# 8led-indicator.net
KiCad netlist of a schematic drawn in EAGLE
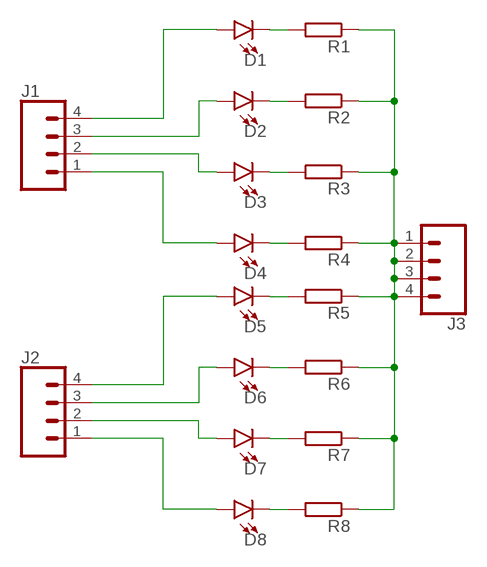
[diagram p0: schematic, sheet 1]

(export (version "E")
  (design (tool "Eeschema 10.0.6"))
  (components
    (comp (ref "D1")
      (value "LED0603")
      (footprint "eagle-import:LED-0603")
      (libsource (lib "eagle-import") (part "LED0603"))
    )
    (comp (ref "D2")
      (value "LED0603")
      (footprint "eagle-import:LED-0603")
      (libsource (lib "eagle-import") (part "LED0603"))
    )
    (comp (ref "D3")
      (value "LED0603")
      (footprint "eagle-import:LED-0603")
      (libsource (lib "eagle-import") (part "LED0603"))
    )
    (comp (ref "D4")
      (value "LED0603")
      (footprint "eagle-import:LED-0603")
      (libsource (lib "eagle-import") (part "LED0603"))
    )
    (comp (ref "D5")
      (value "LED0603")
      (footprint "eagle-import:LED-0603")
      (libsource (lib "eagle-import") (part "LED0603"))
    )
    (comp (ref "D6")
      (value "LED0603")
      (footprint "eagle-import:LED-0603")
      (libsource (lib "eagle-import") (part "LED0603"))
    )
    (comp (ref "D7")
      (value "LED0603")
      (footprint "eagle-import:LED-0603")
      (libsource (lib "eagle-import") (part "LED0603"))
    )
    (comp (ref "D8")
      (value "LED0603")
      (footprint "eagle-import:LED-0603")
      (libsource (lib "eagle-import") (part "LED0603"))
    )
    (comp (ref "J1")
      (value "CONN_04LOCK")
      (footprint "eagle-import:1X04_LOCK")
      (libsource (lib "eagle-import") (part "CONN_04LOCK"))
    )
    (comp (ref "J2")
      (value "CONN_04LOCK")
      (footprint "eagle-import:1X04_LOCK")
      (libsource (lib "eagle-import") (part "CONN_04LOCK"))
    )
    (comp (ref "J3")
      (value "CONN_04LOCK")
      (footprint "eagle-import:1X04_LOCK")
      (libsource (lib "eagle-import") (part "CONN_04LOCK"))
    )
    (comp (ref "R1")
      (value "RESISTOR-EU_R0603")
      (footprint "eagle-import:R0603")
      (libsource (lib "eagle-import") (part "RESISTOR-EU_R0603"))
    )
    (comp (ref "R2")
      (value "RESISTOR-EU_R0603")
      (footprint "eagle-import:R0603")
      (libsource (lib "eagle-import") (part "RESISTOR-EU_R0603"))
    )
    (comp (ref "R3")
      (value "RESISTOR-EU_R0603")
      (footprint "eagle-import:R0603")
      (libsource (lib "eagle-import") (part "RESISTOR-EU_R0603"))
    )
    (comp (ref "R4")
      (value "RESISTOR-EU_R0603")
      (footprint "eagle-import:R0603")
      (libsource (lib "eagle-import") (part "RESISTOR-EU_R0603"))
    )
    (comp (ref "R5")
      (value "RESISTOR-EU_R0603")
      (footprint "eagle-import:R0603")
      (libsource (lib "eagle-import") (part "RESISTOR-EU_R0603"))
    )
    (comp (ref "R6")
      (value "RESISTOR-EU_R0603")
      (footprint "eagle-import:R0603")
      (libsource (lib "eagle-import") (part "RESISTOR-EU_R0603"))
    )
    (comp (ref "R7")
      (value "RESISTOR-EU_R0603")
      (footprint "eagle-import:R0603")
      (libsource (lib "eagle-import") (part "RESISTOR-EU_R0603"))
    )
    (comp (ref "R8")
      (value "RESISTOR-EU_R0603")
      (footprint "eagle-import:R0603")
      (libsource (lib "eagle-import") (part "RESISTOR-EU_R0603"))
    )
  )
  (nets
    (net (code "1") (name "Net-(D1-PadA)") (class "Default")
      (node (ref "D1") (pin "A") (pinfunction "A_A") (pintype "passive"))
      (node (ref "J1") (pin "4") (pinfunction "4_4") (pintype "passive"))
    )
    (net (code "2") (name "Net-(D1-PadC)") (class "Default")
      (node (ref "D1") (pin "C") (pinfunction "C_C") (pintype "passive"))
      (node (ref "R1") (pin "2") (pinfunction "2_2") (pintype "passive"))
    )
    (net (code "3") (name "Net-(D2-PadA)") (class "Default")
      (node (ref "D2") (pin "A") (pinfunction "A_A") (pintype "passive"))
      (node (ref "J1") (pin "3") (pinfunction "3_3") (pintype "passive"))
    )
    (net (code "4") (name "Net-(D2-PadC)") (class "Default")
      (node (ref "D2") (pin "C") (pinfunction "C_C") (pintype "passive"))
      (node (ref "R2") (pin "2") (pinfunction "2_2") (pintype "passive"))
    )
    (net (code "5") (name "Net-(D3-PadA)") (class "Default")
      (node (ref "D3") (pin "A") (pinfunction "A_A") (pintype "passive"))
      (node (ref "J1") (pin "2") (pinfunction "2_2") (pintype "passive"))
    )
    (net (code "6") (name "Net-(D3-PadC)") (class "Default")
      (node (ref "D3") (pin "C") (pinfunction "C_C") (pintype "passive"))
      (node (ref "R3") (pin "2") (pinfunction "2_2") (pintype "passive"))
    )
    (net (code "7") (name "Net-(D4-PadA)") (class "Default")
      (node (ref "D4") (pin "A") (pinfunction "A_A") (pintype "passive"))
      (node (ref "J1") (pin "1") (pinfunction "1_1") (pintype "passive"))
    )
    (net (code "8") (name "Net-(D4-PadC)") (class "Default")
      (node (ref "D4") (pin "C") (pinfunction "C_C") (pintype "passive"))
      (node (ref "R4") (pin "2") (pinfunction "2_2") (pintype "passive"))
    )
    (net (code "9") (name "Net-(D5-PadA)") (class "Default")
      (node (ref "D5") (pin "A") (pinfunction "A_A") (pintype "passive"))
      (node (ref "J2") (pin "4") (pinfunction "4_4") (pintype "passive"))
    )
    (net (code "10") (name "Net-(D5-PadC)") (class "Default")
      (node (ref "D5") (pin "C") (pinfunction "C_C") (pintype "passive"))
      (node (ref "R5") (pin "2") (pinfunction "2_2") (pintype "passive"))
    )
    (net (code "11") (name "Net-(D6-PadA)") (class "Default")
      (node (ref "D6") (pin "A") (pinfunction "A_A") (pintype "passive"))
      (node (ref "J2") (pin "3") (pinfunction "3_3") (pintype "passive"))
    )
    (net (code "12") (name "Net-(D6-PadC)") (class "Default")
      (node (ref "D6") (pin "C") (pinfunction "C_C") (pintype "passive"))
      (node (ref "R6") (pin "2") (pinfunction "2_2") (pintype "passive"))
    )
    (net (code "13") (name "Net-(D7-PadA)") (class "Default")
      (node (ref "D7") (pin "A") (pinfunction "A_A") (pintype "passive"))
      (node (ref "J2") (pin "2") (pinfunction "2_2") (pintype "passive"))
    )
    (net (code "14") (name "Net-(D7-PadC)") (class "Default")
      (node (ref "D7") (pin "C") (pinfunction "C_C") (pintype "passive"))
      (node (ref "R7") (pin "2") (pinfunction "2_2") (pintype "passive"))
    )
    (net (code "15") (name "Net-(D8-PadA)") (class "Default")
      (node (ref "D8") (pin "A") (pinfunction "A_A") (pintype "passive"))
      (node (ref "J2") (pin "1") (pinfunction "1_1") (pintype "passive"))
    )
    (net (code "16") (name "Net-(D8-PadC)") (class "Default")
      (node (ref "D8") (pin "C") (pinfunction "C_C") (pintype "passive"))
      (node (ref "R8") (pin "2") (pinfunction "2_2") (pintype "passive"))
    )
    (net (code "17") (name "Net-(J3-Pad1)") (class "Default")
      (node (ref "J3") (pin "1") (pinfunction "1_1") (pintype "passive"))
      (node (ref "J3") (pin "2") (pinfunction "2_2") (pintype "passive"))
      (node (ref "J3") (pin "3") (pinfunction "3_3") (pintype "passive"))
      (node (ref "J3") (pin "4") (pinfunction "4_4") (pintype "passive"))
      (node (ref "R1") (pin "1") (pinfunction "1_1") (pintype "passive"))
      (node (ref "R2") (pin "1") (pinfunction "1_1") (pintype "passive"))
      (node (ref "R3") (pin "1") (pinfunction "1_1") (pintype "passive"))
      (node (ref "R4") (pin "1") (pinfunction "1_1") (pintype "passive"))
      (node (ref "R5") (pin "1") (pinfunction "1_1") (pintype "passive"))
      (node (ref "R6") (pin "1") (pinfunction "1_1") (pintype "passive"))
      (node (ref "R7") (pin "1") (pinfunction "1_1") (pintype "passive"))
      (node (ref "R8") (pin "1") (pinfunction "1_1") (pintype "passive"))
    )
  )
)
